# feather-power-switch-breakout-mk-1_0.net
KiCad netlist of a schematic drawn in EAGLE
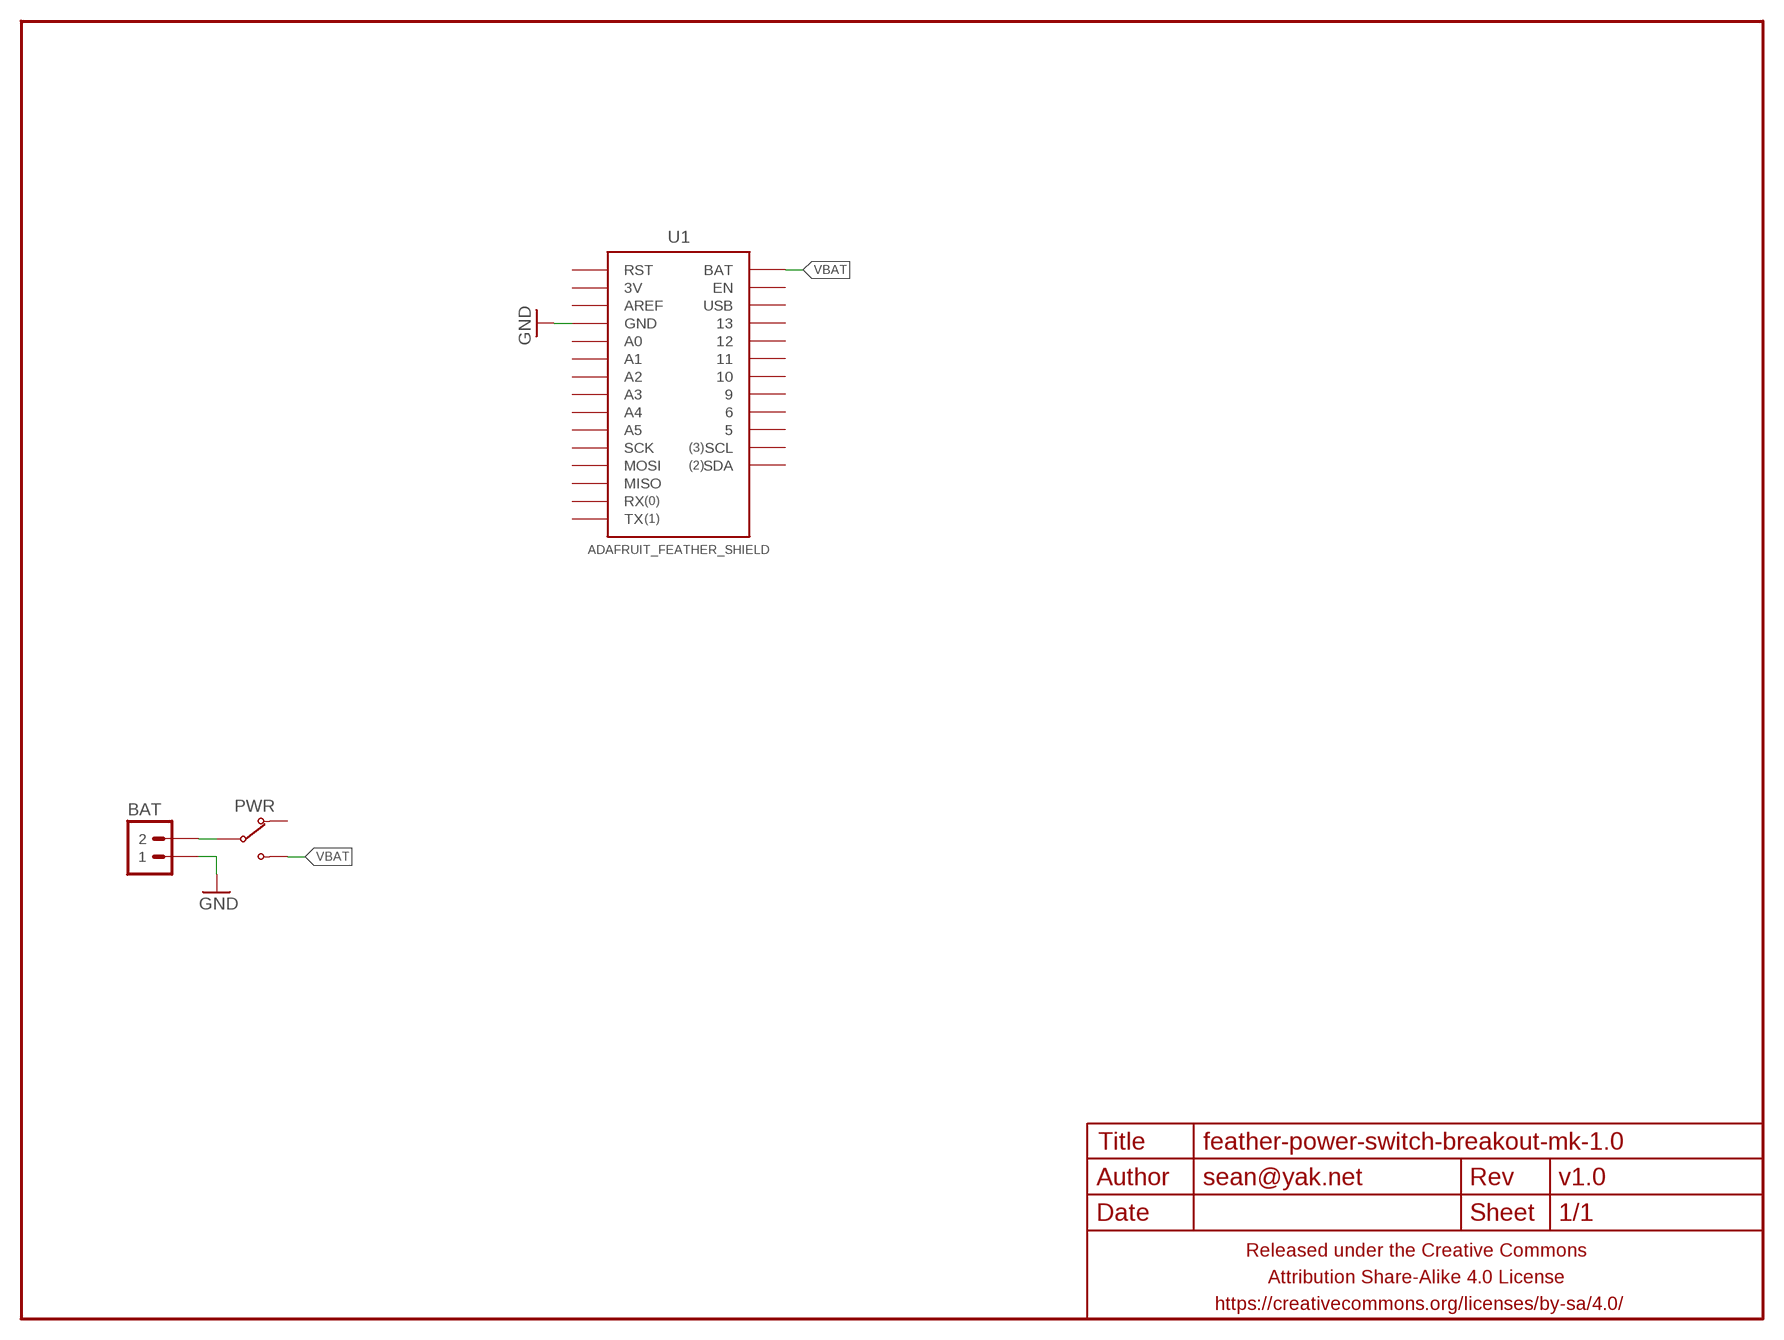
[diagram p0: schematic, sheet 1]

(export (version "E")
  (design (tool "Eeschema 10.0.6"))
  (components
    (comp (ref "BAT")
      (value "M02JST-PTH-RA-R+")
      (footprint "eagle-import:JST-2-PH-RA-PTH-R+")
      (libsource (lib "eagle-import") (part "M02JST-PTH-RA-R+"))
    )
    (comp (ref "FRAME1")
      (value "FRAME-LETTERNO_PACKAGE")
      (footprint "eagle-import:DUMMY")
      (fields (field (name "DESIGNER") "sean@yak.net") (field (name "VERSION") "v1.0"))
      (libsource (lib "eagle-import") (part "FRAME-LETTERNO_PACKAGE"))
    )
    (comp (ref "PWR")
      (value "SWITCH-SPDTPTH-RA-2.54MM")
      (footprint "eagle-import:SPDT-RA-2.54MM")
      (libsource (lib "eagle-import") (part "SWITCH-SPDTPTH-RA-2.54MM"))
    )
    (comp (ref "U1")
      (value "ADAFRUIT_FEATHER_SHIELD")
      (footprint "eagle-import:ADAFRUIT_FEATHER")
      (libsource (lib "eagle-import") (part "ADAFRUIT_FEATHER_SHIELD"))
    )
  )
  (nets
    (net (code "1") (name "GND") (class "Default")
      (node (ref "BAT") (pin "1") (pinfunction "1_1") (pintype "passive"))
      (node (ref "U1") (pin "GND@0") (pinfunction "GND_GND@0") (pintype "bidirectional"))
      (node (ref "U1") (pin "GND@1") (pinfunction "GND_GND@1") (pintype "bidirectional"))
    )
    (net (code "2") (name "Net-(PWR-COM)") (class "Default")
      (node (ref "BAT") (pin "2") (pinfunction "2_2") (pintype "passive"))
      (node (ref "PWR") (pin "2") (pinfunction "COM_2") (pintype "passive"))
    )
    (net (code "3") (name "VBAT") (class "Default")
      (node (ref "PWR") (pin "3") (pinfunction "NO_3") (pintype "passive"))
      (node (ref "U1") (pin "BAT") (pinfunction "BAT_BAT") (pintype "bidirectional"))
    )
    (net (code "4") (name "unconnected-(PWR-NC-Pad1)") (class "Default")
      (node (ref "PWR") (pin "1") (pinfunction "NC_1") (pintype "passive"))
    )
    (net (code "5") (name "unconnected-(U1-Pad3V)") (class "Default")
      (node (ref "U1") (pin "3V") (pinfunction "3V_3V") (pintype "bidirectional"))
    )
    (net (code "6") (name "unconnected-(U1-Pad5)") (class "Default")
      (node (ref "U1") (pin "5") (pinfunction "5_5") (pintype "bidirectional"))
    )
    (net (code "7") (name "unconnected-(U1-Pad6)") (class "Default")
      (node (ref "U1") (pin "6") (pinfunction "6_6") (pintype "bidirectional"))
    )
    (net (code "8") (name "unconnected-(U1-Pad9)") (class "Default")
      (node (ref "U1") (pin "9") (pinfunction "9_9") (pintype "bidirectional"))
    )
    (net (code "9") (name "unconnected-(U1-Pad10)") (class "Default")
      (node (ref "U1") (pin "10") (pinfunction "10_10") (pintype "bidirectional"))
    )
    (net (code "10") (name "unconnected-(U1-Pad11)") (class "Default")
      (node (ref "U1") (pin "11") (pinfunction "11_11") (pintype "bidirectional"))
    )
    (net (code "11") (name "unconnected-(U1-Pad12)") (class "Default")
      (node (ref "U1") (pin "12") (pinfunction "12_12") (pintype "bidirectional"))
    )
    (net (code "12") (name "unconnected-(U1-Pad13)") (class "Default")
      (node (ref "U1") (pin "13") (pinfunction "13_13") (pintype "bidirectional"))
    )
    (net (code "13") (name "unconnected-(U1-PadA0)") (class "Default")
      (node (ref "U1") (pin "A0") (pinfunction "A0_A0") (pintype "bidirectional"))
    )
    (net (code "14") (name "unconnected-(U1-PadA1)") (class "Default")
      (node (ref "U1") (pin "A1") (pinfunction "A1_A1") (pintype "bidirectional"))
    )
    (net (code "15") (name "unconnected-(U1-PadA2)") (class "Default")
      (node (ref "U1") (pin "A2") (pinfunction "A2_A2") (pintype "bidirectional"))
    )
    (net (code "16") (name "unconnected-(U1-PadA3)") (class "Default")
      (node (ref "U1") (pin "A3") (pinfunction "A3_A3") (pintype "bidirectional"))
    )
    (net (code "17") (name "unconnected-(U1-PadA4)") (class "Default")
      (node (ref "U1") (pin "A4") (pinfunction "A4_A4") (pintype "bidirectional"))
    )
    (net (code "18") (name "unconnected-(U1-PadA5)") (class "Default")
      (node (ref "U1") (pin "A5") (pinfunction "A5_A5") (pintype "bidirectional"))
    )
    (net (code "19") (name "unconnected-(U1-PadAREF)") (class "Default")
      (node (ref "U1") (pin "AREF") (pinfunction "AREF_AREF") (pintype "bidirectional"))
    )
    (net (code "20") (name "unconnected-(U1-PadEN)") (class "Default")
      (node (ref "U1") (pin "EN") (pinfunction "EN_EN") (pintype "bidirectional"))
    )
    (net (code "21") (name "unconnected-(U1-PadMISO)") (class "Default")
      (node (ref "U1") (pin "MISO") (pinfunction "MISO_MISO") (pintype "bidirectional"))
    )
    (net (code "22") (name "unconnected-(U1-PadMOSI)") (class "Default")
      (node (ref "U1") (pin "MOSI") (pinfunction "MOSI_MOSI") (pintype "bidirectional"))
    )
    (net (code "23") (name "unconnected-(U1-PadRST)") (class "Default")
      (node (ref "U1") (pin "RST") (pinfunction "RST_RST") (pintype "bidirectional"))
    )
    (net (code "24") (name "unconnected-(U1-PadRX)") (class "Default")
      (node (ref "U1") (pin "RX") (pinfunction "RX_RX") (pintype "bidirectional"))
    )
    (net (code "25") (name "unconnected-(U1-PadSCK)") (class "Default")
      (node (ref "U1") (pin "SCK") (pinfunction "SCK_SCK") (pintype "bidirectional"))
    )
    (net (code "26") (name "unconnected-(U1-PadSCL)") (class "Default")
      (node (ref "U1") (pin "SCL") (pinfunction "SCL_SCL") (pintype "bidirectional"))
    )
    (net (code "27") (name "unconnected-(U1-PadSDA)") (class "Default")
      (node (ref "U1") (pin "SDA") (pinfunction "SDA_SDA") (pintype "bidirectional"))
    )
    (net (code "28") (name "unconnected-(U1-PadTX)") (class "Default")
      (node (ref "U1") (pin "TX") (pinfunction "TX_TX") (pintype "bidirectional"))
    )
    (net (code "29") (name "unconnected-(U1-PadUSB)") (class "Default")
      (node (ref "U1") (pin "USB") (pinfunction "USB_USB") (pintype "bidirectional"))
    )
  )
)
